# interface2ad.net
KiCad netlist of a schematic drawn in Altium Designer
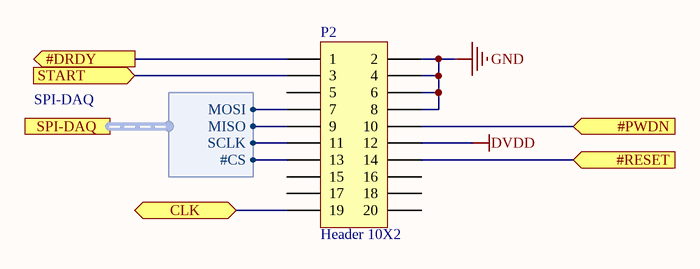
[diagram p0: interface2ad.SchDoc]

(export (version "E")
  (design (tool "Eeschema 10.0.6"))
  (components
    (comp (ref "P2")
      (value "Header 10X2")
      (footprint "61002021121")
      (description "Header, 10-Pin, Dual row")
      (fields (field (name "PUBLISHER") "Altium Limited"))
      (libsource (lib "Miscellaneous Connectors") (part "Header 10X2"))
    )
  )
  (nets
    (net (code "2") (name "/#CS") (class "Default")
      (node (ref "P2") (pin "13") (pinfunction "13_13") (pintype "passive"))
    )
    (net (code "3") (name "/#DRDY") (class "Default")
      (node (ref "P2") (pin "1") (pinfunction "1_1") (pintype "passive"))
    )
    (net (code "4") (name "/#PWDN") (class "Default")
      (node (ref "P2") (pin "10") (pinfunction "10_10") (pintype "passive"))
    )
    (net (code "5") (name "/#RESET") (class "Default")
      (node (ref "P2") (pin "14") (pinfunction "14_14") (pintype "passive"))
    )
    (net (code "6") (name "/CLK") (class "Default")
      (node (ref "P2") (pin "19") (pinfunction "19_19") (pintype "passive"))
    )
    (net (code "7") (name "/MISO") (class "Default")
      (node (ref "P2") (pin "9") (pinfunction "9_9") (pintype "passive"))
    )
    (net (code "8") (name "/MOSI") (class "Default")
      (node (ref "P2") (pin "7") (pinfunction "7_7") (pintype "passive"))
    )
    (net (code "9") (name "/SCLK") (class "Default")
      (node (ref "P2") (pin "11") (pinfunction "11_11") (pintype "passive"))
    )
    (net (code "10") (name "/START") (class "Default")
      (node (ref "P2") (pin "3") (pinfunction "3_3") (pintype "passive"))
    )
    (net (code "12") (name "DVDD") (class "Default")
      (node (ref "P2") (pin "12") (pinfunction "12_12") (pintype "passive"))
    )
    (net (code "13") (name "GND") (class "Default")
      (node (ref "P2") (pin "2") (pinfunction "2_2") (pintype "passive"))
      (node (ref "P2") (pin "4") (pinfunction "4_4") (pintype "passive"))
      (node (ref "P2") (pin "6") (pinfunction "6_6") (pintype "passive"))
      (node (ref "P2") (pin "8") (pinfunction "8_8") (pintype "passive"))
    )
    (net (code "14") (name "unconnected-(P2-Pad5)") (class "Default")
      (node (ref "P2") (pin "5") (pinfunction "5_5") (pintype "passive"))
    )
    (net (code "15") (name "unconnected-(P2-Pad15)") (class "Default")
      (node (ref "P2") (pin "15") (pinfunction "15_15") (pintype "passive"))
    )
    (net (code "16") (name "unconnected-(P2-Pad16)") (class "Default")
      (node (ref "P2") (pin "16") (pinfunction "16_16") (pintype "passive"))
    )
    (net (code "17") (name "unconnected-(P2-Pad17)") (class "Default")
      (node (ref "P2") (pin "17") (pinfunction "17_17") (pintype "passive"))
    )
    (net (code "18") (name "unconnected-(P2-Pad18)") (class "Default")
      (node (ref "P2") (pin "18") (pinfunction "18_18") (pintype "passive"))
    )
    (net (code "19") (name "unconnected-(P2-Pad20)") (class "Default")
      (node (ref "P2") (pin "20") (pinfunction "20_20") (pintype "passive"))
    )
  )
)
